# SubProgrammableBall.net
KiCad netlist of a schematic drawn in EAGLE
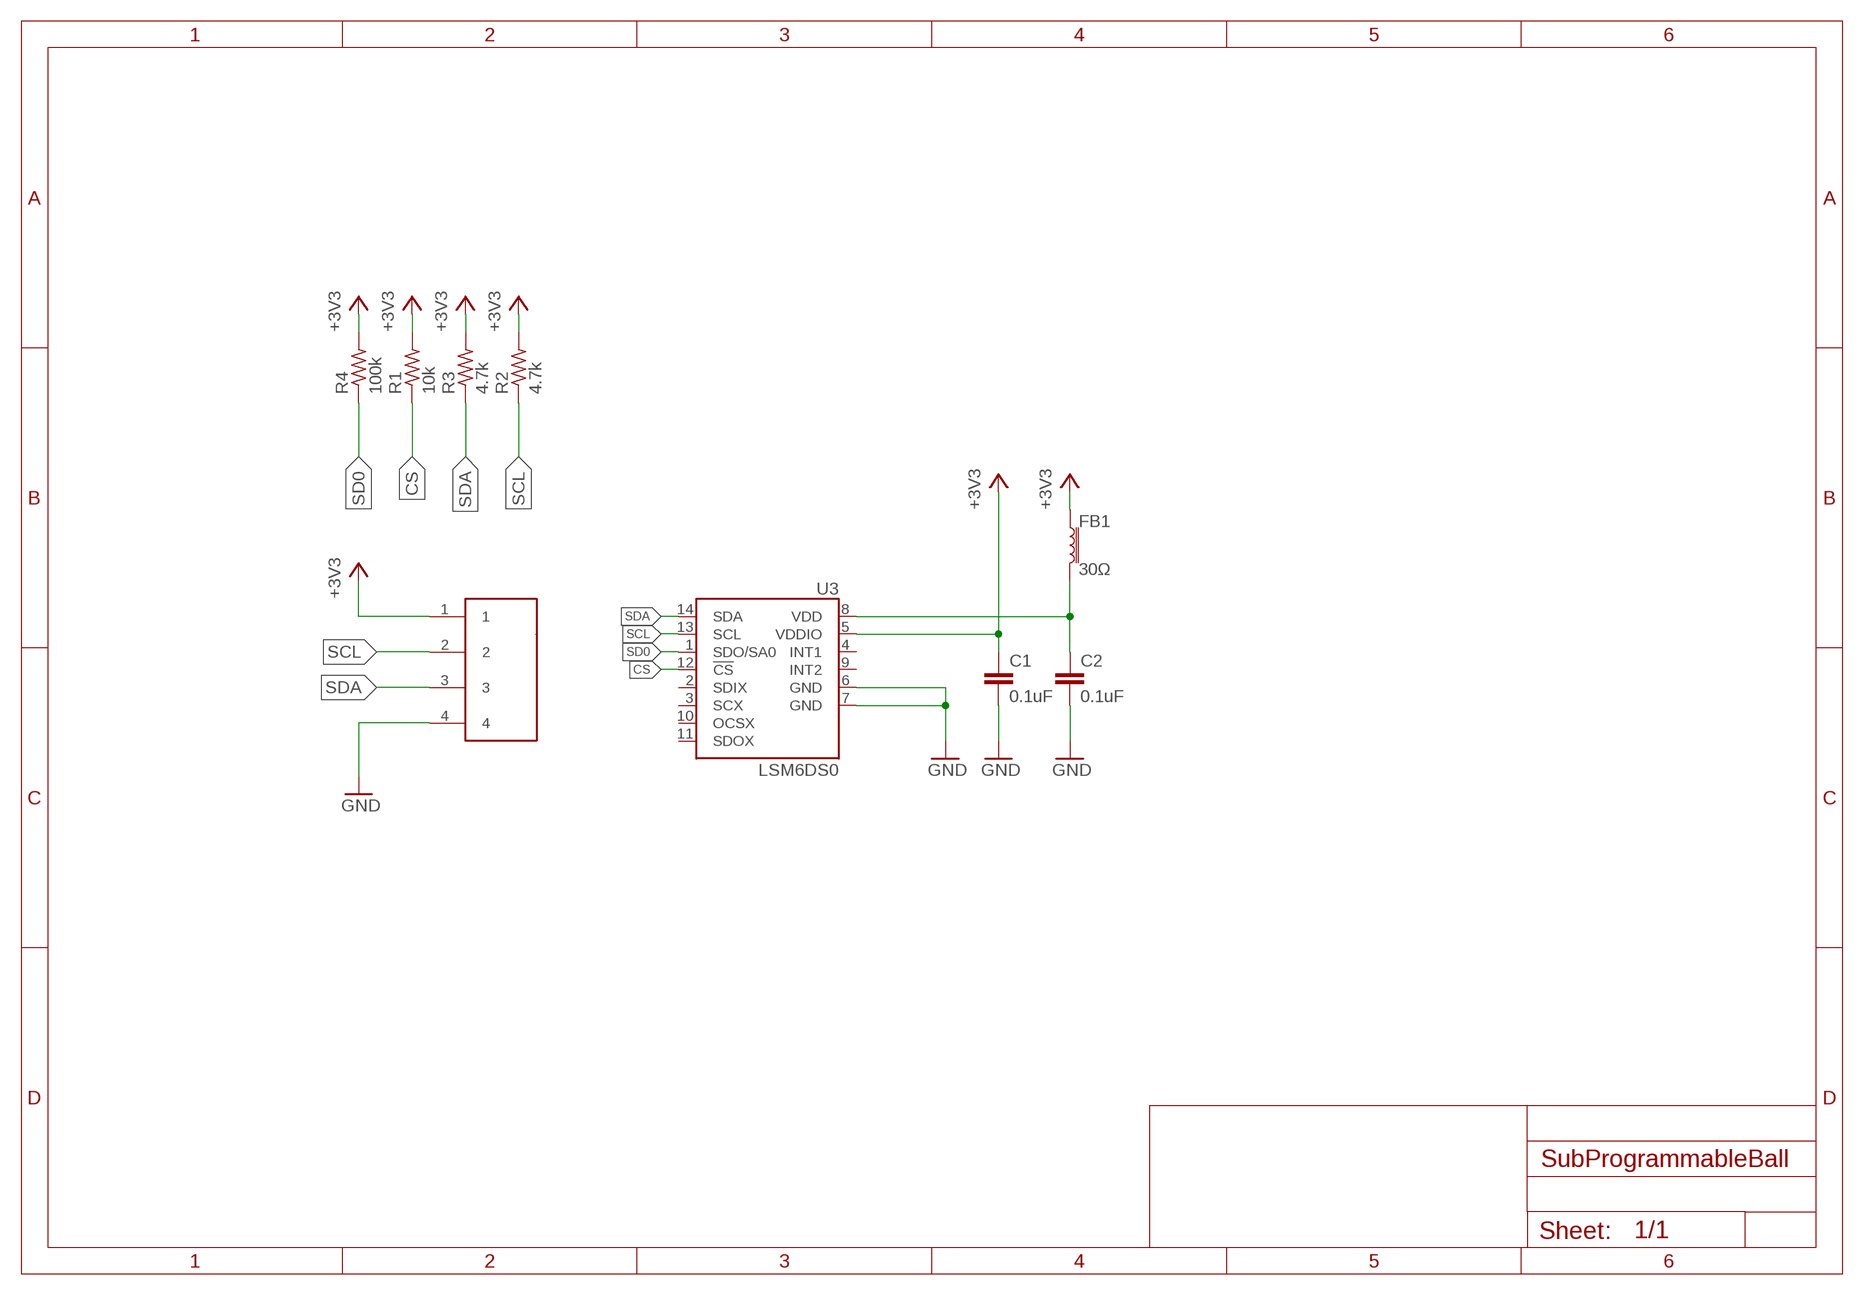
[diagram p0: schematic, sheet 1]

(export (version "E")
  (design (tool "Eeschema 10.0.6"))
  (components
    (comp (ref "C1")
      (value "0.1uF")
      (footprint "eagle-import:C0603")
      (libsource (lib "eagle-import") (part "C-EUC0603"))
    )
    (comp (ref "C2")
      (value "0.1uF")
      (footprint "eagle-import:C0603")
      (libsource (lib "eagle-import") (part "C-EUC0603"))
    )
    (comp (ref "CON1")
      (value "B4B-ZR-SM4-TF")
      (footprint "eagle-import:CONN_B4B-ZR-SM4-TF")
      (libsource (lib "eagle-import") (part "B4B-ZR-SM4-TF"))
    )
    (comp (ref "FB1")
      (value "30Ω")
      (footprint "eagle-import:0603")
      (libsource (lib "eagle-import") (part "FERRITE_BEAD-0603-30Ω-100MHZ"))
    )
    (comp (ref "R1")
      (value "10k")
      (footprint "eagle-import:R0603")
      (libsource (lib "eagle-import") (part "R-US_R0603"))
    )
    (comp (ref "R2")
      (value "4.7k")
      (footprint "eagle-import:R0603")
      (libsource (lib "eagle-import") (part "R-US_R0603"))
    )
    (comp (ref "R3")
      (value "4.7k")
      (footprint "eagle-import:R0603")
      (libsource (lib "eagle-import") (part "R-US_R0603"))
    )
    (comp (ref "R4")
      (value "100k")
      (footprint "eagle-import:R0603")
      (libsource (lib "eagle-import") (part "R-US_R0603"))
    )
    (comp (ref "U3")
      (value "LSM6DS0")
      (footprint "eagle-import:LGA14L")
      (libsource (lib "eagle-import") (part "LSM6DS0"))
    )
  )
  (nets
    (net (code "1") (name "+3V3") (class "Default")
      (node (ref "C1") (pin "1") (pinfunction "1_1") (pintype "passive"))
      (node (ref "CON1") (pin "1") (pinfunction "1_1") (pintype "passive"))
      (node (ref "FB1") (pin "1") (pinfunction "1_1") (pintype "passive"))
      (node (ref "R1") (pin "2") (pinfunction "2_2") (pintype "passive"))
      (node (ref "R2") (pin "2") (pinfunction "2_2") (pintype "passive"))
      (node (ref "R3") (pin "2") (pinfunction "2_2") (pintype "passive"))
      (node (ref "R4") (pin "2") (pinfunction "2_2") (pintype "passive"))
      (node (ref "U3") (pin "5") (pinfunction "VDDIO_5") (pintype "bidirectional"))
    )
    (net (code "2") (name "CS") (class "Default")
      (node (ref "R1") (pin "1") (pinfunction "1_1") (pintype "passive"))
      (node (ref "U3") (pin "12") (pinfunction "~{CS}_12") (pintype "bidirectional"))
    )
    (net (code "3") (name "GND") (class "Default")
      (node (ref "C1") (pin "2") (pinfunction "2_2") (pintype "passive"))
      (node (ref "C2") (pin "2") (pinfunction "2_2") (pintype "passive"))
      (node (ref "CON1") (pin "4") (pinfunction "4_4") (pintype "passive"))
      (node (ref "U3") (pin "6") (pinfunction "GND_6") (pintype "bidirectional"))
      (node (ref "U3") (pin "7") (pinfunction "GND_7") (pintype "bidirectional"))
    )
    (net (code "4") (name "Net-(U3-VDD)") (class "Default")
      (node (ref "C2") (pin "1") (pinfunction "1_1") (pintype "passive"))
      (node (ref "FB1") (pin "2") (pinfunction "2_2") (pintype "passive"))
      (node (ref "U3") (pin "8") (pinfunction "VDD_8") (pintype "bidirectional"))
    )
    (net (code "5") (name "SCL") (class "Default")
      (node (ref "CON1") (pin "2") (pinfunction "2_2") (pintype "passive"))
      (node (ref "R2") (pin "1") (pinfunction "1_1") (pintype "passive"))
      (node (ref "U3") (pin "13") (pinfunction "SCL_13") (pintype "bidirectional"))
    )
    (net (code "6") (name "SD0") (class "Default")
      (node (ref "R4") (pin "1") (pinfunction "1_1") (pintype "passive"))
      (node (ref "U3") (pin "1") (pinfunction "SDO/SA0_1") (pintype "bidirectional"))
    )
    (net (code "7") (name "SDA") (class "Default")
      (node (ref "CON1") (pin "3") (pinfunction "3_3") (pintype "passive"))
      (node (ref "R3") (pin "1") (pinfunction "1_1") (pintype "passive"))
      (node (ref "U3") (pin "14") (pinfunction "SDA_14") (pintype "bidirectional"))
    )
    (net (code "8") (name "unconnected-(U3-INT1-Pad4)") (class "Default")
      (node (ref "U3") (pin "4") (pinfunction "INT1_4") (pintype "bidirectional"))
    )
    (net (code "9") (name "unconnected-(U3-INT2-Pad9)") (class "Default")
      (node (ref "U3") (pin "9") (pinfunction "INT2_9") (pintype "bidirectional"))
    )
    (net (code "10") (name "unconnected-(U3-OCSX-Pad10)") (class "Default")
      (node (ref "U3") (pin "10") (pinfunction "OCSX_10") (pintype "bidirectional"))
    )
    (net (code "11") (name "unconnected-(U3-SCX-Pad3)") (class "Default")
      (node (ref "U3") (pin "3") (pinfunction "SCX_3") (pintype "bidirectional"))
    )
    (net (code "12") (name "unconnected-(U3-SDIX-Pad2)") (class "Default")
      (node (ref "U3") (pin "2") (pinfunction "SDIX_2") (pintype "bidirectional"))
    )
    (net (code "13") (name "unconnected-(U3-SDOX-Pad11)") (class "Default")
      (node (ref "U3") (pin "11") (pinfunction "SDOX_11") (pintype "bidirectional"))
    )
  )
)
